# OutputChannel.net
KiCad netlist of a schematic drawn in Altium Designer
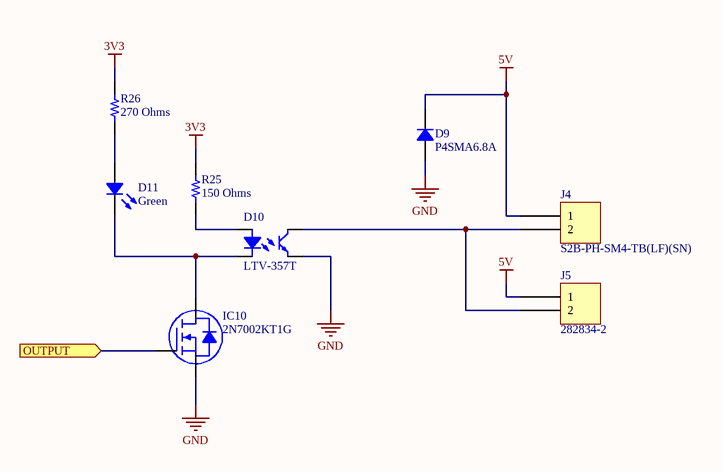
[diagram p0: OutputChannel.SchDoc]

(export (version "E")
  (design (tool "Eeschema 10.0.6"))
  (components
    (comp (ref "D9")
      (value "P4SMA6.8A")
      (footprint "DO214AC SMA")
      (description "TVS DIODE 5.8V 10.5V DO214AC")
      (fields (field (name "MANUFACTURER") "Littelfuse Inc."))
      (libsource (lib "Celestial Altium Library - altium_library") (part "Diode"))
    )
    (comp (ref "D10")
      (value "LTV-357T")
      (footprint "LITEON LTV-357T")
      (description "OPTOISOLATOR 3.75KV TRANS 4-SOP")
      (fields (field (name "MANUFACTURER") "Lite-On Inc."))
      (libsource (lib "Celestial Altium Library - altium_library") (part "Optoisolator"))
    )
    (comp (ref "D11")
      (value "Green")
      (footprint "LED 0603_1608 GREEN")
      (description "LED GREEN CLEAR CHIP SMD")
      (fields (field (name "PART NUMBER") "LTST-C190KGKT") (field (name "MANUFACTURER") "Lite-On Inc."))
      (libsource (lib "Celestial Altium Library - altium_library") (part "LED"))
    )
    (comp (ref "IC10")
      (value "2N7002KT1G")
      (footprint "ON SEMI SOT-23-3")
      (description "MOSFET N-CH 60V 320MA SOT-23")
      (fields (field (name "MANUFACTURER") "ON Semiconductor"))
      (libsource (lib "Celestial Altium Library - altium_library") (part "ON SEMI MOSFET N-CH SOT-23-3"))
    )
    (comp (ref "J4")
      (value "S2B-PH-SM4-TB(LF)(SN)")
      (footprint "JST S2B-PH-SM4-TB")
      (description "CONN HEADER SMD R/A 2POS 2MM")
      (fields (field (name "MANUFACTURER") "JST Sales America Inc."))
      (libsource (lib "Celestial Altium Library - altium_library") (part "2 Pin"))
    )
    (comp (ref "J5")
      (value "282834-2")
      (footprint "TE 282834-2")
      (description "TERM BLK 2P SIDE ENT 2.54MM PCB")
      (fields (field (name "MANUFACTURER") "TE Connectivity AMP Connectors") (field (name "VOLTAGE") "150V"))
      (libsource (lib "Celestial Altium Library - altium_library") (part "2 Pin"))
    )
    (comp (ref "R25")
      (value "150 Ohms")
      (footprint "RES 0603_1608")
      (description "RES SMD 150 OHM 1% 1/10W 0603")
      (fields
        (field (name "PART NUMBER") "ERJ-3EKF1500V")
        (field (name "MANUFACTURER") "Panasonic Electronic Components")
      )
      (libsource (lib "Celestial Altium Library - altium_library") (part "Resistor"))
    )
    (comp (ref "R26")
      (value "270 Ohms")
      (footprint "RES 0603_1608")
      (description "RES SMD 270 OHM 1% 1/10W 0603")
      (fields
        (field (name "PART NUMBER") "ERJ-3EKF2700V")
        (field (name "MANUFACTURER") "Panasonic Electronic Components")
      )
      (libsource (lib "Celestial Altium Library - altium_library") (part "Resistor"))
    )
  )
  (nets
    (net (code "1") (name "/OUTPUT") (class "Default")
      (node (ref "IC10") (pin "1") (pinfunction "G_1") (pintype "passive"))
    )
    (net (code "2") (name "3V3") (class "Default")
      (node (ref "R25") (pin "2") (pinfunction "2_2") (pintype "passive"))
      (node (ref "R26") (pin "2") (pinfunction "2_2") (pintype "passive"))
    )
    (net (code "3") (name "5V") (class "Default")
      (node (ref "D9") (pin "2") (pinfunction "2_2") (pintype "passive"))
      (node (ref "J4") (pin "1") (pinfunction "1_1") (pintype "passive"))
      (node (ref "J5") (pin "1") (pinfunction "1_1") (pintype "passive"))
    )
    (net (code "4") (name "GND") (class "Default")
      (node (ref "D10") (pin "3") (pinfunction "3_3") (pintype "passive"))
      (node (ref "D9") (pin "1") (pinfunction "1_1") (pintype "passive"))
      (node (ref "IC10") (pin "2") (pinfunction "S_2") (pintype "passive"))
    )
    (net (code "5") (name "Net-(D10-Pad1)") (class "Default")
      (node (ref "D10") (pin "1") (pinfunction "1_1") (pintype "passive"))
      (node (ref "R25") (pin "1") (pinfunction "1_1") (pintype "passive"))
    )
    (net (code "6") (name "Net-(D10-Pad4)") (class "Default")
      (node (ref "D10") (pin "4") (pinfunction "4_4") (pintype "passive"))
      (node (ref "J4") (pin "2") (pinfunction "2_2") (pintype "passive"))
      (node (ref "J5") (pin "2") (pinfunction "2_2") (pintype "passive"))
    )
    (net (code "7") (name "Net-(D11-Pad1)") (class "Default")
      (node (ref "D11") (pin "1") (pinfunction "1_1") (pintype "passive"))
      (node (ref "R26") (pin "1") (pinfunction "1_1") (pintype "passive"))
    )
    (net (code "8") (name "Net-(IC10-D)") (class "Default")
      (node (ref "D10") (pin "2") (pinfunction "2_2") (pintype "passive"))
      (node (ref "D11") (pin "2") (pinfunction "2_2") (pintype "passive"))
      (node (ref "IC10") (pin "3") (pinfunction "D_3") (pintype "passive"))
    )
  )
)
